# sch_driver.net
KiCad netlist of a schematic drawn in Altium Designer
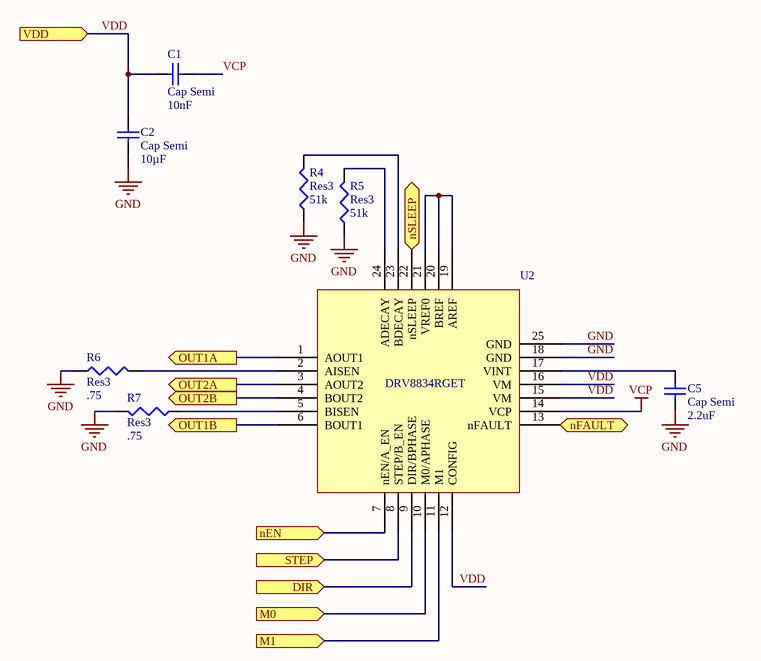
[diagram p0: sch_driver.SchDoc]

(export (version "E")
  (design (tool "Eeschema 10.0.6"))
  (components
    (comp (ref "C1")
      (value "Cap Semi")
      (footprint "C1206")
      (description "Capacitor (Semiconductor SIM Model)")
      (fields (field (name "ALTIUM_VALUE") "10nF") (field (name "PUBLISHER") "Altium Limited"))
      (libsource (lib "Miscellaneous Devices") (part "Cap Semi"))
    )
    (comp (ref "C2")
      (value "Cap Semi")
      (footprint "C1206")
      (description "Capacitor (Semiconductor SIM Model)")
      (fields (field (name "ALTIUM_VALUE") "10µF") (field (name "PUBLISHER") "Altium Limited"))
      (libsource (lib "Miscellaneous Devices") (part "Cap Semi"))
    )
    (comp (ref "C5")
      (value "Cap Semi")
      (footprint "C1206")
      (description "Capacitor (Semiconductor SIM Model)")
      (fields (field (name "ALTIUM_VALUE") "2.2uF") (field (name "PUBLISHER") "Altium Limited"))
      (libsource (lib "Miscellaneous Devices") (part "Cap Semi"))
    )
    (comp (ref "R4")
      (value "Res3")
      (footprint "C1206")
      (description "Resistor")
      (fields (field (name "ALTIUM_VALUE") "51k") (field (name "PUBLISHER") "Altium Limited"))
      (libsource (lib "Miscellaneous Devices") (part "Res3"))
    )
    (comp (ref "R5")
      (value "Res3")
      (footprint "C1206")
      (description "Resistor")
      (fields (field (name "ALTIUM_VALUE") "51k") (field (name "PUBLISHER") "Altium Limited"))
      (libsource (lib "Miscellaneous Devices") (part "Res3"))
    )
    (comp (ref "R6")
      (value "Res3")
      (footprint "C1206")
      (description "Resistor")
      (fields (field (name "ALTIUM_VALUE") ".75") (field (name "PUBLISHER") "Altium Limited"))
      (libsource (lib "Miscellaneous Devices") (part "Res3"))
    )
    (comp (ref "R7")
      (value "Res3")
      (footprint "C1206")
      (description "Resistor")
      (fields (field (name "ALTIUM_VALUE") ".75") (field (name "PUBLISHER") "Altium Limited"))
      (libsource (lib "Miscellaneous Devices") (part "Res3"))
    )
    (comp (ref "U2")
      (value "DRV8834RGET")
      (footprint "QFN24")
      (libsource (lib "SCH_LIB_EPM") (part "DRV8834RGET"))
    )
  )
  (nets
    (net (code "1") (name "/DIR") (class "Default")
      (node (ref "U2") (pin "9") (pinfunction "DIR/BPHASE_9") (pintype "passive"))
    )
    (net (code "2") (name "/M0") (class "Default")
      (node (ref "U2") (pin "10") (pinfunction "M0/APHASE_10") (pintype "passive"))
    )
    (net (code "3") (name "/M1") (class "Default")
      (node (ref "U2") (pin "11") (pinfunction "M1_11") (pintype "passive"))
    )
    (net (code "4") (name "/OUT1A") (class "Default")
      (node (ref "U2") (pin "1") (pinfunction "AOUT1_1") (pintype "passive"))
    )
    (net (code "5") (name "/OUT1B") (class "Default")
      (node (ref "U2") (pin "6") (pinfunction "BOUT1_6") (pintype "passive"))
    )
    (net (code "6") (name "/OUT2A") (class "Default")
      (node (ref "U2") (pin "3") (pinfunction "AOUT2_3") (pintype "passive"))
    )
    (net (code "7") (name "/OUT2B") (class "Default")
      (node (ref "U2") (pin "4") (pinfunction "BOUT2_4") (pintype "passive"))
    )
    (net (code "8") (name "/STEP") (class "Default")
      (node (ref "U2") (pin "8") (pinfunction "STEP/B_EN_8") (pintype "passive"))
    )
    (net (code "9") (name "/VDD") (class "Default")
      (node (ref "C1") (pin "2") (pinfunction "2_2") (pintype "passive"))
      (node (ref "C2") (pin "1") (pinfunction "1_1") (pintype "passive"))
      (node (ref "U2") (pin "12") (pinfunction "CONFIG_12") (pintype "passive"))
      (node (ref "U2") (pin "15") (pinfunction "VM_15") (pintype "passive"))
      (node (ref "U2") (pin "16") (pinfunction "VM_16") (pintype "passive"))
    )
    (net (code "10") (name "/nEN") (class "Default")
      (node (ref "U2") (pin "7") (pinfunction "nEN/A_EN_7") (pintype "passive"))
    )
    (net (code "11") (name "/nFAULT") (class "Default")
      (node (ref "U2") (pin "13") (pinfunction "nFAULT_13") (pintype "passive"))
    )
    (net (code "12") (name "/nSLEEP") (class "Default")
      (node (ref "U2") (pin "22") (pinfunction "nSLEEP_22") (pintype "passive"))
    )
    (net (code "13") (name "GND") (class "Default")
      (node (ref "C2") (pin "2") (pinfunction "2_2") (pintype "passive"))
      (node (ref "C5") (pin "1") (pinfunction "1_1") (pintype "passive"))
      (node (ref "R4") (pin "1") (pinfunction "1_1") (pintype "passive"))
      (node (ref "R5") (pin "1") (pinfunction "1_1") (pintype "passive"))
      (node (ref "R6") (pin "1") (pinfunction "1_1") (pintype "passive"))
      (node (ref "R7") (pin "2") (pinfunction "2_2") (pintype "passive"))
      (node (ref "U2") (pin "18") (pinfunction "GND_18") (pintype "passive"))
      (node (ref "U2") (pin "25") (pinfunction "GND_25") (pintype "passive"))
    )
    (net (code "14") (name "Net-(U2-ADECAY)") (class "Default")
      (node (ref "R5") (pin "2") (pinfunction "2_2") (pintype "passive"))
      (node (ref "U2") (pin "24") (pinfunction "ADECAY_24") (pintype "passive"))
    )
    (net (code "15") (name "Net-(U2-AISEN)") (class "Default")
      (node (ref "R6") (pin "2") (pinfunction "2_2") (pintype "passive"))
      (node (ref "U2") (pin "2") (pinfunction "AISEN_2") (pintype "passive"))
    )
    (net (code "16") (name "Net-(U2-AREF)") (class "Default")
      (node (ref "U2") (pin "19") (pinfunction "AREF_19") (pintype "passive"))
      (node (ref "U2") (pin "20") (pinfunction "BREF_20") (pintype "passive"))
      (node (ref "U2") (pin "21") (pinfunction "VREF0_21") (pintype "passive"))
    )
    (net (code "17") (name "Net-(U2-BDECAY)") (class "Default")
      (node (ref "R4") (pin "2") (pinfunction "2_2") (pintype "passive"))
      (node (ref "U2") (pin "23") (pinfunction "BDECAY_23") (pintype "passive"))
    )
    (net (code "18") (name "Net-(U2-BISEN)") (class "Default")
      (node (ref "R7") (pin "1") (pinfunction "1_1") (pintype "passive"))
      (node (ref "U2") (pin "5") (pinfunction "BISEN_5") (pintype "passive"))
    )
    (net (code "19") (name "Net-(U2-VINT)") (class "Default")
      (node (ref "C5") (pin "2") (pinfunction "2_2") (pintype "passive"))
      (node (ref "U2") (pin "17") (pinfunction "VINT_17") (pintype "passive"))
    )
    (net (code "20") (name "VCP") (class "Default")
      (node (ref "C1") (pin "1") (pinfunction "1_1") (pintype "passive"))
      (node (ref "U2") (pin "14") (pinfunction "VCP_14") (pintype "passive"))
    )
  )
)
